# Simple-Bug-BC557.net
KiCad netlist of a schematic drawn in EAGLE
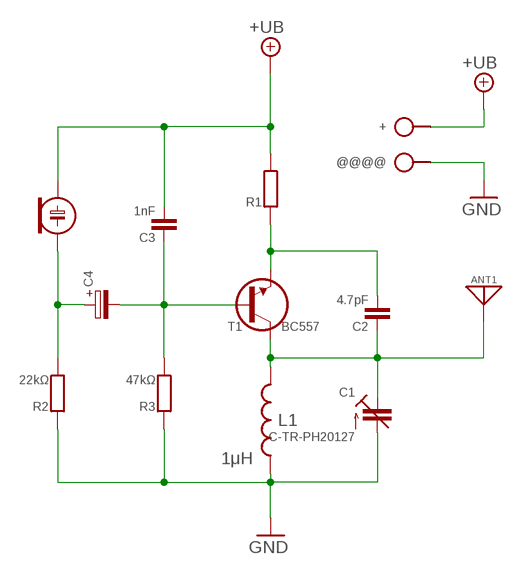
[diagram p0: schematic, sheet 1]

(export (version "E")
  (design (tool "Eeschema 10.0.6"))
  (components
    (comp (ref "+")
      (value "SPAD")
      (footprint "eagle-import:SPAD")
      (libsource (lib "eagle-import") (part "SPAD"))
    )
    (comp (ref "@@@@")
      (value "SPAD")
      (footprint "eagle-import:SPAD")
      (libsource (lib "eagle-import") (part "SPAD"))
    )
    (comp (ref "ANT1")
      (value "ANT")
      (footprint "eagle-import:SPAD")
      (libsource (lib "eagle-import") (part "ANT"))
    )
    (comp (ref "C1")
      (value "C-TR-PH20127")
      (footprint "eagle-import:TRIM808-45")
      (libsource (lib "eagle-import") (part "C-TR-PH20127-45-2P23"))
    )
    (comp (ref "C2")
      (value "4.7pF")
      (footprint "eagle-import:C050-020X036")
      (libsource (lib "eagle-import") (part "C050-020X036"))
    )
    (comp (ref "C3")
      (value "1nF")
      (footprint "eagle-import:C050-020X036")
      (libsource (lib "eagle-import") (part "C050-020X036"))
    )
    (comp (ref "C4")
      (value "CPOLE2,5-3")
      (footprint "eagle-import:E2,5-3")
      (libsource (lib "eagle-import") (part "CPOLE2,5-3"))
    )
    (comp (ref "ECM")
      (value "ECM-5")
      (footprint "eagle-import:ECM-5")
      (libsource (lib "eagle-import") (part "ECM-5"))
    )
    (comp (ref "L1")
      (value "1μH")
      (footprint "eagle-import:L-04_7")
      (libsource (lib "eagle-import") (part "L04/7"))
    )
    (comp (ref "R1")
      (value "R0202V")
      (footprint "eagle-import:0202V")
      (libsource (lib "eagle-import") (part "R0202V"))
    )
    (comp (ref "R2")
      (value "22kΩ")
      (footprint "eagle-import:0202_5")
      (libsource (lib "eagle-import") (part "R0202/5"))
    )
    (comp (ref "R3")
      (value "47kΩ")
      (footprint "eagle-import:0202_5")
      (libsource (lib "eagle-import") (part "R0202/5"))
    )
    (comp (ref "T1")
      (value "BC557")
      (footprint "eagle-import:TO92-CBE-A")
      (libsource (lib "eagle-import") (part "BC547CBE-A"))
    )
  )
  (nets
    (net (code "1") (name "+UB") (class "Default")
      (node (ref "+") (pin "1") (pinfunction "P$1_1") (pintype "passive"))
      (node (ref "C3") (pin "2") (pinfunction "2_2") (pintype "passive"))
      (node (ref "ECM") (pin "1") (pinfunction "+_1") (pintype "passive"))
      (node (ref "R1") (pin "2") (pinfunction "2_2") (pintype "passive"))
    )
    (net (code "2") (name "GND") (class "Default")
      (node (ref "@@@@") (pin "1") (pinfunction "P$1_1") (pintype "passive"))
      (node (ref "C1") (pin "3") (pinfunction "A_3") (pintype "passive"))
      (node (ref "L1") (pin "2") (pinfunction "2_2") (pintype "passive"))
      (node (ref "R2") (pin "1") (pinfunction "1_1") (pintype "passive"))
      (node (ref "R3") (pin "1") (pinfunction "1_1") (pintype "passive"))
    )
    (net (code "3") (name "Net-(C1-E)") (class "Default")
      (node (ref "ANT1") (pin "1") (pinfunction "1_1") (pintype "output"))
      (node (ref "C1") (pin "2") (pinfunction "E_2") (pintype "passive"))
      (node (ref "C2") (pin "1") (pinfunction "1_1") (pintype "passive"))
      (node (ref "L1") (pin "1") (pinfunction "1_1") (pintype "passive"))
      (node (ref "T1") (pin "C") (pinfunction "C_C") (pintype "passive"))
    )
    (net (code "4") (name "Net-(C2-Pad2)") (class "Default")
      (node (ref "C2") (pin "2") (pinfunction "2_2") (pintype "passive"))
      (node (ref "R1") (pin "1") (pinfunction "1_1") (pintype "passive"))
      (node (ref "T1") (pin "E") (pinfunction "E_E") (pintype "passive"))
    )
    (net (code "5") (name "Net-(C3-Pad1)") (class "Default")
      (node (ref "C3") (pin "1") (pinfunction "1_1") (pintype "passive"))
      (node (ref "C4") (pin "-") (pinfunction "-_-") (pintype "passive"))
      (node (ref "R3") (pin "2") (pinfunction "2_2") (pintype "passive"))
      (node (ref "T1") (pin "B") (pinfunction "B_B") (pintype "passive"))
    )
    (net (code "6") (name "Net-(ECM--)") (class "Default")
      (node (ref "C4") (pin "+") (pinfunction "+_+") (pintype "passive"))
      (node (ref "ECM") (pin "2") (pinfunction "-_2") (pintype "passive"))
      (node (ref "R2") (pin "2") (pinfunction "2_2") (pintype "passive"))
    )
  )
)
